# Keyboard.net
KiCad netlist of a schematic drawn in Altium Designer
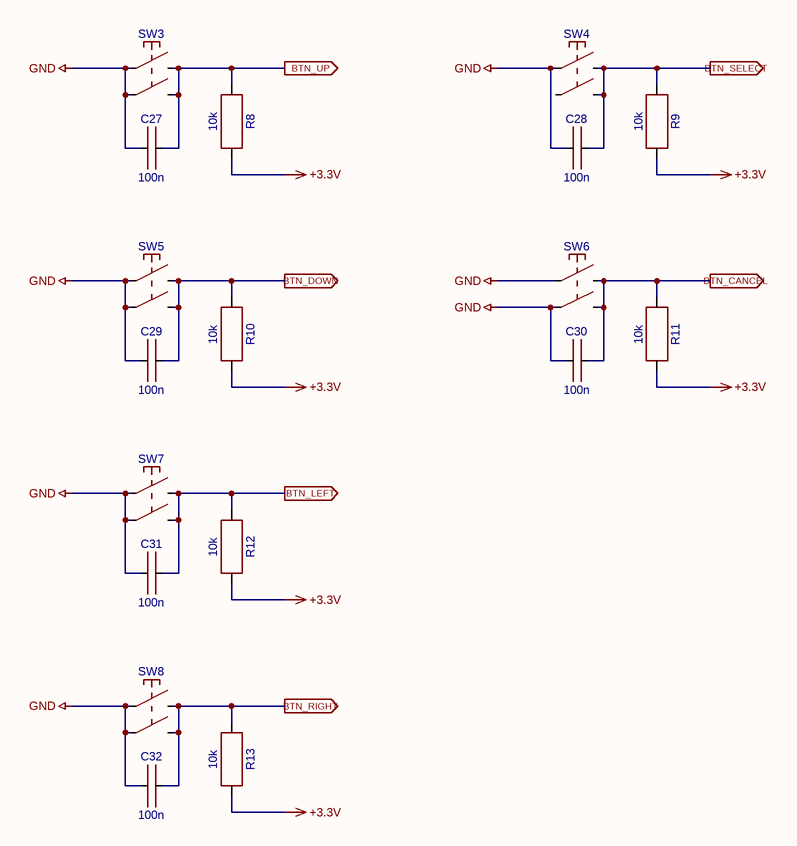
[diagram p0: Keyboard.SchDoc]

(export (version "E")
  (design (tool "Eeschema 10.0.6"))
  (components
    (comp (ref "C27")
      (value "100n")
      (footprint "CAPC1608X09N")
      (description "GRM188R71E104KA01D")
      (libsource (lib "Capasitors") (part "C0603-100n-25V-X7R-10%"))
    )
    (comp (ref "C28")
      (value "100n")
      (footprint "CAPC1608X09N")
      (description "GRM188R71E104KA01D")
      (libsource (lib "Capasitors") (part "C0603-100n-25V-X7R-10%"))
    )
    (comp (ref "C29")
      (value "100n")
      (footprint "CAPC1608X09N")
      (description "GRM188R71E104KA01D")
      (libsource (lib "Capasitors") (part "C0603-100n-25V-X7R-10%"))
    )
    (comp (ref "C30")
      (value "100n")
      (footprint "CAPC1608X09N")
      (description "GRM188R71E104KA01D")
      (libsource (lib "Capasitors") (part "C0603-100n-25V-X7R-10%"))
    )
    (comp (ref "C31")
      (value "100n")
      (footprint "CAPC1608X09N")
      (description "GRM188R71E104KA01D")
      (libsource (lib "Capasitors") (part "C0603-100n-25V-X7R-10%"))
    )
    (comp (ref "C32")
      (value "100n")
      (footprint "CAPC1608X09N")
      (description "GRM188R71E104KA01D")
      (libsource (lib "Capasitors") (part "C0603-100n-25V-X7R-10%"))
    )
    (comp (ref "R8")
      (value "10k")
      (footprint "RESC2012X05N")
      (libsource (lib "Resistors") (part "R-0805-10k-5%"))
    )
    (comp (ref "R9")
      (value "10k")
      (footprint "RESC2012X05N")
      (libsource (lib "Resistors") (part "R-0805-10k-5%"))
    )
    (comp (ref "R10")
      (value "10k")
      (footprint "RESC2012X05N")
      (libsource (lib "Resistors") (part "R-0805-10k-5%"))
    )
    (comp (ref "R11")
      (value "10k")
      (footprint "RESC2012X05N")
      (libsource (lib "Resistors") (part "R-0805-10k-5%"))
    )
    (comp (ref "R12")
      (value "10k")
      (footprint "RESC2012X05N")
      (libsource (lib "Resistors") (part "R-0805-10k-5%"))
    )
    (comp (ref "R13")
      (value "10k")
      (footprint "RESC2012X05N")
      (libsource (lib "Resistors") (part "R-0805-10k-5%"))
    )
    (comp (ref "SW3")
      (value "KLS7-TS6601-11-180")
      (footprint "KLS7-TS6601-11-180")
      (description "(IT-1102K) Кнопка тактовая прямая 6х6х11мм")
      (libsource (lib "Buttons") (part "KLS7-TS6601-11-180"))
    )
    (comp (ref "SW4")
      (value "KLS7-TS6601-11-180")
      (footprint "KLS7-TS6601-11-180")
      (description "(IT-1102K) Кнопка тактовая прямая 6х6х11мм")
      (libsource (lib "Buttons") (part "KLS7-TS6601-11-180"))
    )
    (comp (ref "SW5")
      (value "KLS7-TS6601-11-180")
      (footprint "KLS7-TS6601-11-180")
      (description "(IT-1102K) Кнопка тактовая прямая 6х6х11мм")
      (libsource (lib "Buttons") (part "KLS7-TS6601-11-180"))
    )
    (comp (ref "SW6")
      (value "KLS7-TS6601-11-180")
      (footprint "KLS7-TS6601-11-180")
      (description "(IT-1102K) Кнопка тактовая прямая 6х6х11мм")
      (libsource (lib "Buttons") (part "KLS7-TS6601-11-180"))
    )
    (comp (ref "SW7")
      (value "KLS7-TS6601-11-180")
      (footprint "KLS7-TS6601-11-180")
      (description "(IT-1102K) Кнопка тактовая прямая 6х6х11мм")
      (libsource (lib "Buttons") (part "KLS7-TS6601-11-180"))
    )
    (comp (ref "SW8")
      (value "KLS7-TS6601-11-180")
      (footprint "KLS7-TS6601-11-180")
      (description "(IT-1102K) Кнопка тактовая прямая 6х6х11мм")
      (libsource (lib "Buttons") (part "KLS7-TS6601-11-180"))
    )
  )
  (nets
    (net (code "1") (name "+3.3V") (class "Default")
      (node (ref "R10") (pin "2") (pinfunction "2_2") (pintype "passive"))
      (node (ref "R11") (pin "2") (pinfunction "2_2") (pintype "passive"))
      (node (ref "R12") (pin "2") (pinfunction "2_2") (pintype "passive"))
      (node (ref "R13") (pin "2") (pinfunction "2_2") (pintype "passive"))
      (node (ref "R8") (pin "2") (pinfunction "2_2") (pintype "passive"))
      (node (ref "R9") (pin "2") (pinfunction "2_2") (pintype "passive"))
    )
    (net (code "2") (name "/BTN_CANCEL") (class "Default")
      (node (ref "C30") (pin "2") (pinfunction "2_2") (pintype "passive"))
      (node (ref "R11") (pin "1") (pinfunction "1_1") (pintype "passive"))
      (node (ref "SW6") (pin "1") (pinfunction "1_1") (pintype "passive"))
      (node (ref "SW6") (pin "3") (pinfunction "3_3") (pintype "passive"))
    )
    (net (code "3") (name "/BTN_DOWN") (class "Default")
      (node (ref "C29") (pin "2") (pinfunction "2_2") (pintype "passive"))
      (node (ref "R10") (pin "1") (pinfunction "1_1") (pintype "passive"))
      (node (ref "SW5") (pin "1") (pinfunction "1_1") (pintype "passive"))
      (node (ref "SW5") (pin "3") (pinfunction "3_3") (pintype "passive"))
    )
    (net (code "4") (name "/BTN_LEFT") (class "Default")
      (node (ref "C31") (pin "2") (pinfunction "2_2") (pintype "passive"))
      (node (ref "R12") (pin "1") (pinfunction "1_1") (pintype "passive"))
      (node (ref "SW7") (pin "1") (pinfunction "1_1") (pintype "passive"))
      (node (ref "SW7") (pin "3") (pinfunction "3_3") (pintype "passive"))
    )
    (net (code "5") (name "/BTN_RIGHT") (class "Default")
      (node (ref "C32") (pin "2") (pinfunction "2_2") (pintype "passive"))
      (node (ref "R13") (pin "1") (pinfunction "1_1") (pintype "passive"))
      (node (ref "SW8") (pin "1") (pinfunction "1_1") (pintype "passive"))
      (node (ref "SW8") (pin "3") (pinfunction "3_3") (pintype "passive"))
    )
    (net (code "6") (name "/BTN_SELECT") (class "Default")
      (node (ref "C28") (pin "2") (pinfunction "2_2") (pintype "passive"))
      (node (ref "R9") (pin "1") (pinfunction "1_1") (pintype "passive"))
      (node (ref "SW4") (pin "1") (pinfunction "1_1") (pintype "passive"))
      (node (ref "SW4") (pin "3") (pinfunction "3_3") (pintype "passive"))
    )
    (net (code "7") (name "/BTN_UP") (class "Default")
      (node (ref "C27") (pin "2") (pinfunction "2_2") (pintype "passive"))
      (node (ref "R8") (pin "1") (pinfunction "1_1") (pintype "passive"))
      (node (ref "SW3") (pin "1") (pinfunction "1_1") (pintype "passive"))
      (node (ref "SW3") (pin "3") (pinfunction "3_3") (pintype "passive"))
    )
    (net (code "8") (name "GND") (class "Default")
      (node (ref "C27") (pin "1") (pinfunction "1_1") (pintype "passive"))
      (node (ref "C28") (pin "1") (pinfunction "1_1") (pintype "passive"))
      (node (ref "C29") (pin "1") (pinfunction "1_1") (pintype "passive"))
      (node (ref "C30") (pin "1") (pinfunction "1_1") (pintype "passive"))
      (node (ref "C31") (pin "1") (pinfunction "1_1") (pintype "passive"))
      (node (ref "C32") (pin "1") (pinfunction "1_1") (pintype "passive"))
      (node (ref "SW3") (pin "0") (pinfunction "0_0") (pintype "passive"))
      (node (ref "SW3") (pin "2") (pinfunction "2_2") (pintype "passive"))
      (node (ref "SW4") (pin "0") (pinfunction "0_0") (pintype "passive"))
      (node (ref "SW5") (pin "0") (pinfunction "0_0") (pintype "passive"))
      (node (ref "SW5") (pin "2") (pinfunction "2_2") (pintype "passive"))
      (node (ref "SW6") (pin "0") (pinfunction "0_0") (pintype "passive"))
      (node (ref "SW6") (pin "2") (pinfunction "2_2") (pintype "passive"))
      (node (ref "SW7") (pin "0") (pinfunction "0_0") (pintype "passive"))
      (node (ref "SW7") (pin "2") (pinfunction "2_2") (pintype "passive"))
      (node (ref "SW8") (pin "0") (pinfunction "0_0") (pintype "passive"))
      (node (ref "SW8") (pin "2") (pinfunction "2_2") (pintype "passive"))
    )
    (net (code "9") (name "unconnected-(SW4-Pad2)") (class "Default")
      (node (ref "SW4") (pin "2") (pinfunction "2_2") (pintype "passive"))
    )
  )
)
